# TM_fan_driver.net
KiCad netlist of a schematic drawn in EasyEDA Pro
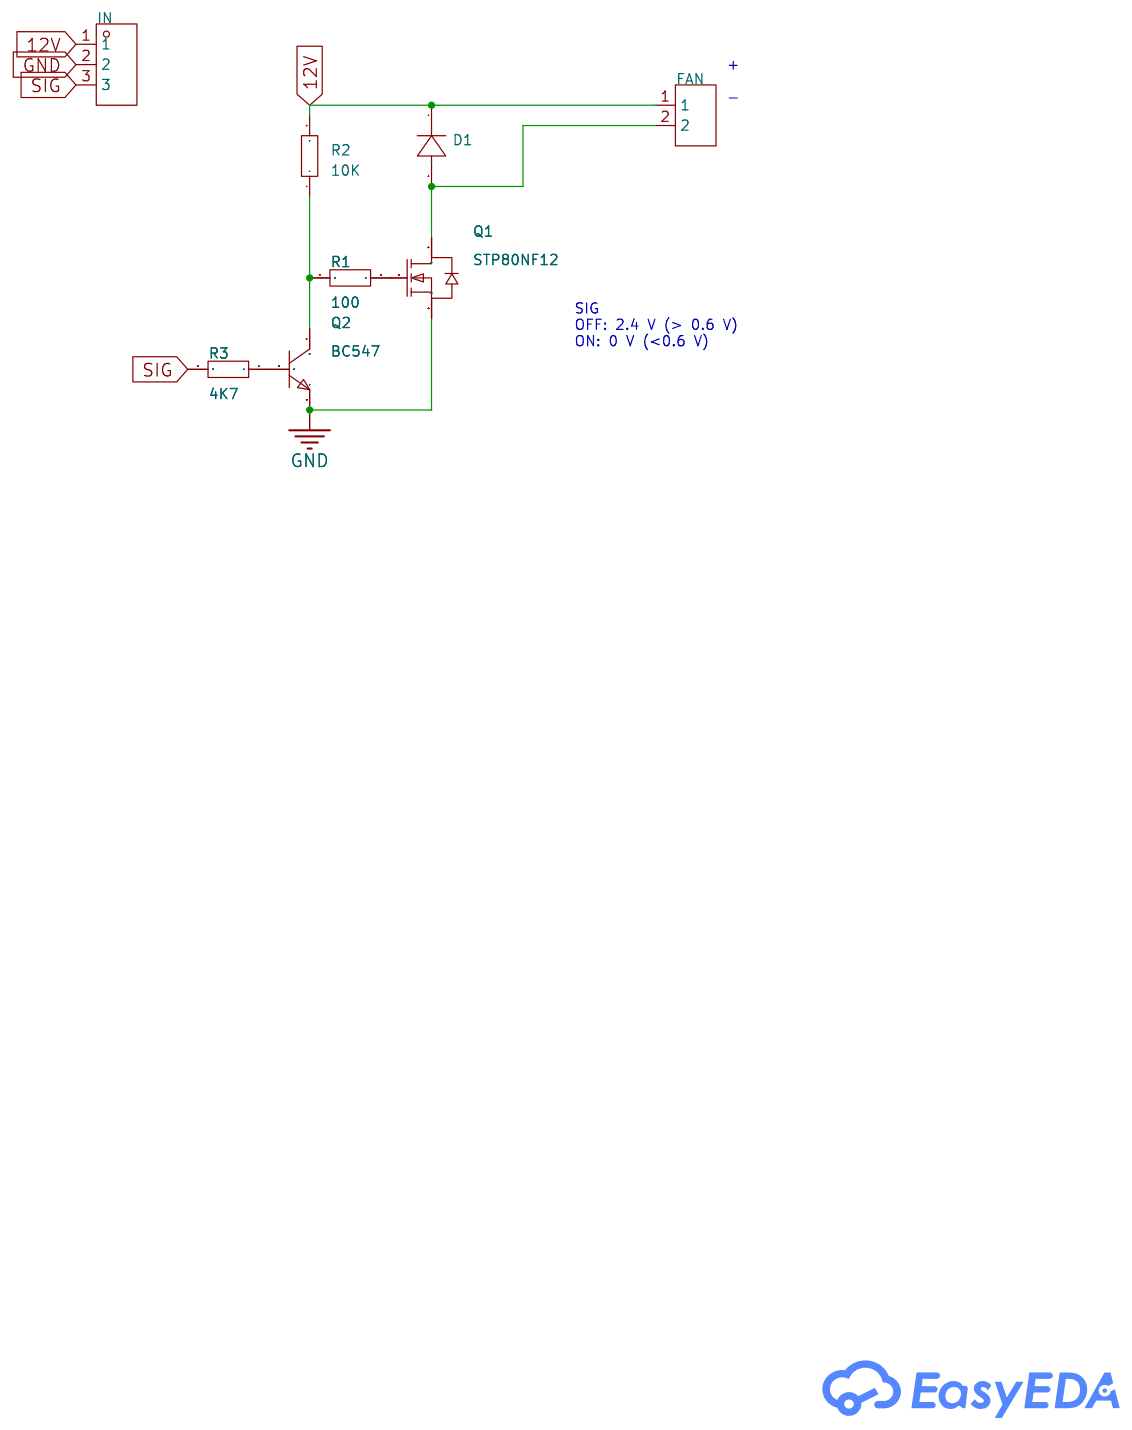
[diagram p0: schematic sheet]

(export (version "E")
  (design (tool "Eeschema 10.0.6"))
  (components
    (comp (ref "D1")
      (value "~")
      (footprint "easyedapro:SMA_L4.4-W2.8-LS5.4-RD")
      (libsource (lib "easyedapro") (part "D_1N4007"))
    )
    (comp (ref "FAN")
      (value "XY-B2B-PH-K-S")
      (footprint "easyedapro:CONN-TH_B2B-PH-K-S")
      (fields (field (name "Manufacturer") "XYECONN(辛译)"))
      (libsource (lib "easyedapro") (part "XY-B2B-PH-K-S"))
    )
    (comp (ref "IN")
      (value "B3B-PH-KL(LF)(SN)")
      (footprint "easyedapro:CONN-TH_B3B-PH-KL-LF-SN")
      (fields (field (name "Manufacturer") "JST"))
      (libsource (lib "easyedapro") (part "B3B-PH-KL(LF)(SN)"))
    )
    (comp (ref "Q1")
      (value "STP80NF12")
      (footprint "easyedapro:TO-220-3_L10.0-W4.5-P2.54-L")
      (fields (field (name "Manufacturer") "ST(意法半导体)"))
      (libsource (lib "easyedapro") (part "STP80NF12"))
    )
    (comp (ref "Q2")
      (value "BC547")
      (footprint "easyedapro:TO-92-3_L4.9-W3.7-P1.27-L")
      (fields (field (name "Manufacturer") "CJ(江苏长电/长晶)"))
      (libsource (lib "easyedapro") (part "BC547_C47089404"))
    )
    (comp (ref "R1") (value "100") (footprint "easyedapro:R0603") (libsource (lib "easyedapro") (part "Res")))
    (comp (ref "R2") (value "10K") (footprint "easyedapro:R0603") (libsource (lib "easyedapro") (part "Res")))
    (comp (ref "R3") (value "4K7") (footprint "easyedapro:R0603") (libsource (lib "easyedapro") (part "Res")))
  )
  (nets
    (net (code "1") (name "12V") (class "Default")
      (node (ref "D1") (pin "1") (pinfunction "K_1") (pintype "input"))
      (node (ref "FAN") (pin "1") (pinfunction "1_1") (pintype "unspecified"))
      (node (ref "IN") (pin "1") (pinfunction "1_1") (pintype "unspecified"))
      (node (ref "R2") (pin "2") (pinfunction "2_2") (pintype "input"))
    )
    (net (code "2") (name "GND") (class "Default")
      (node (ref "IN") (pin "2") (pinfunction "2_2") (pintype "unspecified"))
      (node (ref "Q1") (pin "3") (pinfunction "S_3") (pintype "unspecified"))
      (node (ref "Q2") (pin "3") (pinfunction "E_3") (pintype "input"))
    )
    (net (code "3") (name "Net-(D1-A)") (class "Default")
      (node (ref "D1") (pin "2") (pinfunction "A_2") (pintype "input"))
      (node (ref "FAN") (pin "2") (pinfunction "2_2") (pintype "unspecified"))
      (node (ref "Q1") (pin "2") (pinfunction "D_2") (pintype "unspecified"))
    )
    (net (code "4") (name "Net-(Q1-G)") (class "Default")
      (node (ref "Q1") (pin "1") (pinfunction "G_1") (pintype "unspecified"))
      (node (ref "R1") (pin "2") (pinfunction "2_2") (pintype "input"))
    )
    (net (code "5") (name "Net-(Q2-B)") (class "Default")
      (node (ref "Q2") (pin "2") (pinfunction "B_2") (pintype "input"))
      (node (ref "R3") (pin "1") (pinfunction "1_1") (pintype "input"))
    )
    (net (code "6") (name "Net-(Q2-C)") (class "Default")
      (node (ref "Q2") (pin "1") (pinfunction "C_1") (pintype "input"))
      (node (ref "R1") (pin "1") (pinfunction "1_1") (pintype "input"))
      (node (ref "R2") (pin "1") (pinfunction "1_1") (pintype "input"))
    )
    (net (code "7") (name "SIG") (class "Default")
      (node (ref "IN") (pin "3") (pinfunction "3_3") (pintype "unspecified"))
      (node (ref "R3") (pin "2") (pinfunction "2_2") (pintype "input"))
    )
  )
)
